# 17_-ETH_CONNECTOR.net
KiCad netlist of a schematic drawn in Altium Designer
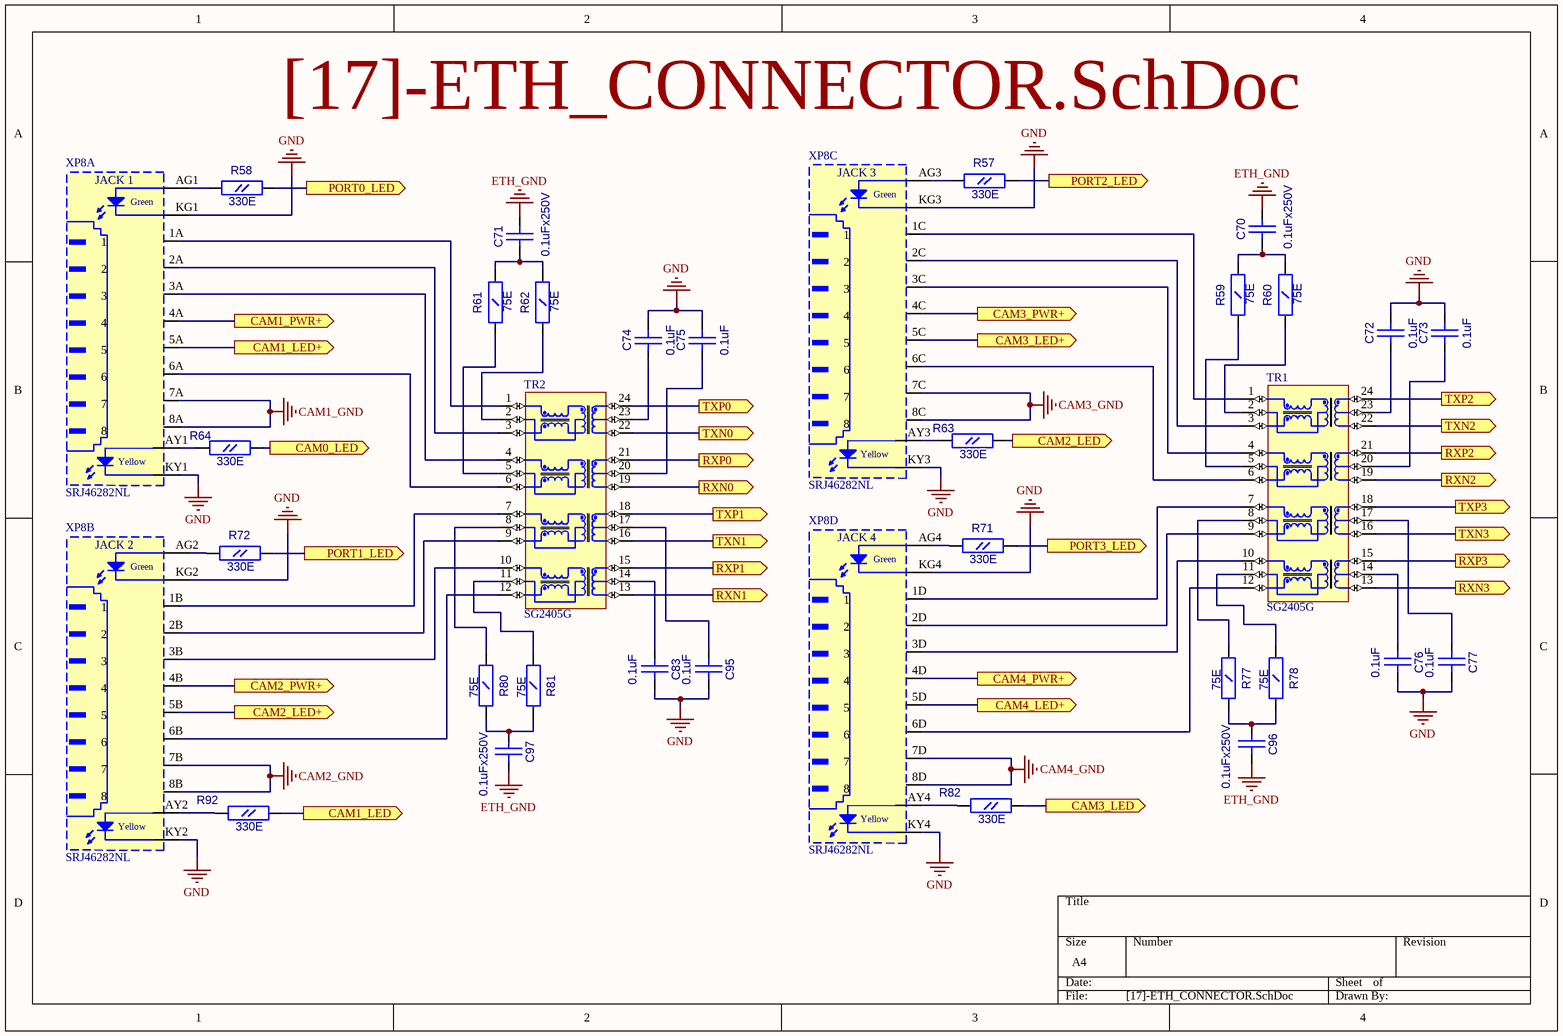
[diagram p0: [17]-ETH_CONNECTOR.SchDoc]

(export (version "E")
  (design (tool "Eeschema 10.0.6"))
  (components
    (comp (ref "C70")
      (value "0.1uFx250V")
      (footprint "CC1206")
      (description "CC1206")
      (libsource (lib "fizik_lib (1)") (part "CC1206"))
    )
    (comp (ref "C71")
      (value "0.1uFx250V")
      (footprint "CC1206")
      (description "CC1206")
      (libsource (lib "fizik_lib (1)") (part "CC1206"))
    )
    (comp (ref "C72")
      (value "0.1uF")
      (footprint "CC0603")
      (description "CC0603")
      (libsource (lib "fizik_lib") (part "CC0603"))
    )
    (comp (ref "C73")
      (value "0.1uF")
      (footprint "CC0603")
      (description "CC0603")
      (libsource (lib "fizik_lib") (part "CC0603"))
    )
    (comp (ref "C74")
      (value "0.1uF")
      (footprint "CC0603")
      (description "CC0603")
      (libsource (lib "fizik_lib") (part "CC0603"))
    )
    (comp (ref "C75")
      (value "0.1uF")
      (footprint "CC0603")
      (description "CC0603")
      (libsource (lib "fizik_lib") (part "CC0603"))
    )
    (comp (ref "C76")
      (value "0.1uF")
      (footprint "CC0603")
      (description "CC0603")
      (libsource (lib "fizik_lib") (part "CC0603"))
    )
    (comp (ref "C77")
      (value "0.1uF")
      (footprint "CC0603")
      (description "CC0603")
      (libsource (lib "fizik_lib") (part "CC0603"))
    )
    (comp (ref "C83")
      (value "0.1uF")
      (footprint "CC0603")
      (description "CC0603")
      (libsource (lib "fizik_lib") (part "CC0603"))
    )
    (comp (ref "C95")
      (value "0.1uF")
      (footprint "CC0603")
      (description "CC0603")
      (libsource (lib "fizik_lib") (part "CC0603"))
    )
    (comp (ref "C96")
      (value "0.1uFx250V")
      (footprint "CC1206")
      (description "CC1206")
      (libsource (lib "fizik_lib (1)") (part "CC1206"))
    )
    (comp (ref "C97")
      (value "0.1uFx250V")
      (footprint "CC1206")
      (description "CC1206")
      (libsource (lib "fizik_lib (1)") (part "CC1206"))
    )
    (comp (ref "R57")
      (value "330E")
      (footprint "RC0603")
      (description "RC0603")
      (libsource (lib "fizik_lib") (part "RC0603"))
    )
    (comp (ref "R58")
      (value "330E")
      (footprint "RC0603")
      (description "RC0603")
      (libsource (lib "fizik_lib") (part "RC0603"))
    )
    (comp (ref "R59")
      (value "75E")
      (footprint "RC1206")
      (description "RC1206")
      (libsource (lib "fizik_lib (1)") (part "RC1206"))
    )
    (comp (ref "R60")
      (value "75E")
      (footprint "RC1206")
      (description "RC1206")
      (libsource (lib "fizik_lib (1)") (part "RC1206"))
    )
    (comp (ref "R61")
      (value "75E")
      (footprint "RC1206")
      (description "RC1206")
      (libsource (lib "fizik_lib (1)") (part "RC1206"))
    )
    (comp (ref "R62")
      (value "75E")
      (footprint "RC1206")
      (description "RC1206")
      (libsource (lib "fizik_lib (1)") (part "RC1206"))
    )
    (comp (ref "R63")
      (value "330E")
      (footprint "RC0603")
      (description "RC0603")
      (libsource (lib "fizik_lib") (part "RC0603"))
    )
    (comp (ref "R64")
      (value "330E")
      (footprint "RC0603")
      (description "RC0603")
      (libsource (lib "fizik_lib") (part "RC0603"))
    )
    (comp (ref "R71")
      (value "330E")
      (footprint "RC0603")
      (description "RC0603")
      (libsource (lib "fizik_lib") (part "RC0603"))
    )
    (comp (ref "R72")
      (value "330E")
      (footprint "RC0603")
      (description "RC0603")
      (libsource (lib "fizik_lib") (part "RC0603"))
    )
    (comp (ref "R77")
      (value "75E")
      (footprint "RC1206")
      (description "RC1206")
      (libsource (lib "fizik_lib (1)") (part "RC1206"))
    )
    (comp (ref "R78")
      (value "75E")
      (footprint "RC1206")
      (description "RC1206")
      (libsource (lib "fizik_lib (1)") (part "RC1206"))
    )
    (comp (ref "R80")
      (value "75E")
      (footprint "RC1206")
      (description "RC1206")
      (libsource (lib "fizik_lib (1)") (part "RC1206"))
    )
    (comp (ref "R81")
      (value "75E")
      (footprint "RC1206")
      (description "RC1206")
      (libsource (lib "fizik_lib (1)") (part "RC1206"))
    )
    (comp (ref "R82")
      (value "330E")
      (footprint "RC0603")
      (description "RC0603")
      (libsource (lib "fizik_lib") (part "RC0603"))
    )
    (comp (ref "R92")
      (value "330E")
      (footprint "RC0603")
      (description "RC0603")
      (libsource (lib "fizik_lib") (part "RC0603"))
    )
    (comp (ref "TR1")
      (value "SG2405G")
      (footprint "SG2405G")
      (description "Ehternet transformer Gigabit or 2 LAN10/100")
      (libsource (lib "fizik_lib (1)") (part "SG2405G"))
    )
    (comp (ref "TR2")
      (value "SG2405G")
      (footprint "SG2405G")
      (description "Ehternet transformer Gigabit or 2 LAN10/100")
      (libsource (lib "fizik_lib (1)") (part "SG2405G"))
    )
    (comp (ref "XP8")
      (value "SRJ46282NL")
      (footprint "SRJ46282NL")
      (libsource (lib "fizik_lib (1)") (part "SRJ46282NL"))
    )
  )
  (nets
    (net (code "1") (name "/CAM0_LED") (class "Default")
      (node (ref "R64") (pin "2") (pinfunction "B_2") (pintype "passive"))
    )
    (net (code "2") (name "/CAM1_LED") (class "Default")
      (node (ref "R92") (pin "2") (pinfunction "B_2") (pintype "passive"))
    )
    (net (code "3") (name "/CAM1_LED+") (class "Default")
      (node (ref "XP8") (pin "5A") (pinfunction "1_5A") (pintype "passive"))
    )
    (net (code "4") (name "/CAM1_PWR+") (class "Default")
      (node (ref "XP8") (pin "4A") (pinfunction "1_4A") (pintype "passive"))
    )
    (net (code "5") (name "/CAM2_LED") (class "Default")
      (node (ref "R63") (pin "2") (pinfunction "B_2") (pintype "passive"))
    )
    (net (code "6") (name "/CAM2_LED+") (class "Default")
      (node (ref "XP8") (pin "5B") (pinfunction "1_5B") (pintype "passive"))
    )
    (net (code "7") (name "/CAM2_PWR+") (class "Default")
      (node (ref "XP8") (pin "4B") (pinfunction "1_4B") (pintype "passive"))
    )
    (net (code "8") (name "/CAM3_LED") (class "Default")
      (node (ref "R82") (pin "2") (pinfunction "B_2") (pintype "passive"))
    )
    (net (code "9") (name "/CAM3_LED+") (class "Default")
      (node (ref "XP8") (pin "5C") (pinfunction "1_5C") (pintype "passive"))
    )
    (net (code "10") (name "/CAM3_PWR+") (class "Default")
      (node (ref "XP8") (pin "4C") (pinfunction "1_4C") (pintype "passive"))
    )
    (net (code "11") (name "/CAM4_LED+") (class "Default")
      (node (ref "XP8") (pin "5D") (pinfunction "1_5D") (pintype "passive"))
    )
    (net (code "12") (name "/CAM4_PWR+") (class "Default")
      (node (ref "XP8") (pin "4D") (pinfunction "1_4D") (pintype "passive"))
    )
    (net (code "13") (name "/PORT0_LED") (class "Default")
      (node (ref "R58") (pin "2") (pinfunction "B_2") (pintype "passive"))
    )
    (net (code "14") (name "/PORT1_LED") (class "Default")
      (node (ref "R72") (pin "2") (pinfunction "B_2") (pintype "passive"))
    )
    (net (code "15") (name "/PORT2_LED") (class "Default")
      (node (ref "R57") (pin "2") (pinfunction "B_2") (pintype "passive"))
    )
    (net (code "16") (name "/PORT3_LED") (class "Default")
      (node (ref "R71") (pin "2") (pinfunction "B_2") (pintype "passive"))
    )
    (net (code "17") (name "/RXN0") (class "Default")
      (node (ref "TR2") (pin "19") (pinfunction "TX1-_19") (pintype "bidirectional"))
    )
    (net (code "18") (name "/RXN1") (class "Default")
      (node (ref "TR2") (pin "13") (pinfunction "RX2-_13") (pintype "bidirectional"))
    )
    (net (code "19") (name "/RXN2") (class "Default")
      (node (ref "TR1") (pin "19") (pinfunction "TX1-_19") (pintype "bidirectional"))
    )
    (net (code "20") (name "/RXN3") (class "Default")
      (node (ref "TR1") (pin "13") (pinfunction "RX2-_13") (pintype "bidirectional"))
    )
    (net (code "21") (name "/RXP0") (class "Default")
      (node (ref "TR2") (pin "21") (pinfunction "TX1+_21") (pintype "bidirectional"))
    )
    (net (code "22") (name "/RXP1") (class "Default")
      (node (ref "TR2") (pin "15") (pinfunction "RX2+_15") (pintype "bidirectional"))
    )
    (net (code "23") (name "/RXP2") (class "Default")
      (node (ref "TR1") (pin "21") (pinfunction "TX1+_21") (pintype "bidirectional"))
    )
    (net (code "24") (name "/RXP3") (class "Default")
      (node (ref "TR1") (pin "15") (pinfunction "RX2+_15") (pintype "bidirectional"))
    )
    (net (code "25") (name "/TXN0") (class "Default")
      (node (ref "TR2") (pin "22") (pinfunction "RX1-_22") (pintype "bidirectional"))
    )
    (net (code "26") (name "/TXN1") (class "Default")
      (node (ref "TR2") (pin "16") (pinfunction "TX2-_16") (pintype "bidirectional"))
    )
    (net (code "27") (name "/TXN2") (class "Default")
      (node (ref "TR1") (pin "22") (pinfunction "RX1-_22") (pintype "bidirectional"))
    )
    (net (code "28") (name "/TXN3") (class "Default")
      (node (ref "TR1") (pin "16") (pinfunction "TX2-_16") (pintype "bidirectional"))
    )
    (net (code "29") (name "/TXP0") (class "Default")
      (node (ref "TR2") (pin "24") (pinfunction "RX1+_24") (pintype "bidirectional"))
    )
    (net (code "30") (name "/TXP1") (class "Default")
      (node (ref "TR2") (pin "18") (pinfunction "TX2+_18") (pintype "bidirectional"))
    )
    (net (code "31") (name "/TXP2") (class "Default")
      (node (ref "TR1") (pin "24") (pinfunction "RX1+_24") (pintype "bidirectional"))
    )
    (net (code "32") (name "/TXP3") (class "Default")
      (node (ref "TR1") (pin "18") (pinfunction "TX2+_18") (pintype "bidirectional"))
    )
    (net (code "33") (name "CAM1_GND") (class "Default")
      (node (ref "XP8") (pin "7A") (pinfunction "1_7A") (pintype "passive"))
      (node (ref "XP8") (pin "8A") (pinfunction "1_8A") (pintype "passive"))
    )
    (net (code "34") (name "CAM2_GND") (class "Default")
      (node (ref "XP8") (pin "7B") (pinfunction "1_7B") (pintype "passive"))
      (node (ref "XP8") (pin "8B") (pinfunction "1_8B") (pintype "passive"))
    )
    (net (code "35") (name "CAM3_GND") (class "Default")
      (node (ref "XP8") (pin "7C") (pinfunction "1_7C") (pintype "passive"))
      (node (ref "XP8") (pin "8C") (pinfunction "1_8C") (pintype "passive"))
    )
    (net (code "36") (name "CAM4_GND") (class "Default")
      (node (ref "XP8") (pin "7D") (pinfunction "1_7D") (pintype "passive"))
      (node (ref "XP8") (pin "8D") (pinfunction "1_8D") (pintype "passive"))
    )
    (net (code "37") (name "ETH_GND") (class "Default")
      (node (ref "C70") (pin "2") (pinfunction "B_2") (pintype "passive"))
      (node (ref "C71") (pin "2") (pinfunction "B_2") (pintype "passive"))
      (node (ref "C96") (pin "2") (pinfunction "B_2") (pintype "passive"))
      (node (ref "C97") (pin "2") (pinfunction "B_2") (pintype "passive"))
    )
    (net (code "38") (name "GND") (class "Default")
      (node (ref "C72") (pin "2") (pinfunction "B_2") (pintype "passive"))
      (node (ref "C73") (pin "2") (pinfunction "B_2") (pintype "passive"))
      (node (ref "C74") (pin "2") (pinfunction "B_2") (pintype "passive"))
      (node (ref "C75") (pin "2") (pinfunction "B_2") (pintype "passive"))
      (node (ref "C76") (pin "2") (pinfunction "B_2") (pintype "passive"))
      (node (ref "C77") (pin "2") (pinfunction "B_2") (pintype "passive"))
      (node (ref "C83") (pin "2") (pinfunction "B_2") (pintype "passive"))
      (node (ref "C95") (pin "2") (pinfunction "B_2") (pintype "passive"))
      (node (ref "XP8") (pin "KG1") (pinfunction "D2_KG1") (pintype "passive"))
      (node (ref "XP8") (pin "KG2") (pinfunction "D2_KG2") (pintype "passive"))
      (node (ref "XP8") (pin "KG3") (pinfunction "D2_KG3") (pintype "passive"))
      (node (ref "XP8") (pin "KG4") (pinfunction "D2_KG4") (pintype "passive"))
      (node (ref "XP8") (pin "KY1") (pinfunction "D4_KY1") (pintype "passive"))
      (node (ref "XP8") (pin "KY2") (pinfunction "D4_KY2") (pintype "passive"))
      (node (ref "XP8") (pin "KY3") (pinfunction "D4_KY3") (pintype "passive"))
      (node (ref "XP8") (pin "KY4") (pinfunction "D4_KY4") (pintype "passive"))
    )
    (net (code "39") (name "Net-(C70-A)") (class "Default")
      (node (ref "C70") (pin "1") (pinfunction "A_1") (pintype "passive"))
      (node (ref "R59") (pin "2") (pinfunction "B_2") (pintype "passive"))
      (node (ref "R60") (pin "2") (pinfunction "B_2") (pintype "passive"))
    )
    (net (code "40") (name "Net-(C71-A)") (class "Default")
      (node (ref "C71") (pin "1") (pinfunction "A_1") (pintype "passive"))
      (node (ref "R61") (pin "2") (pinfunction "B_2") (pintype "passive"))
      (node (ref "R62") (pin "2") (pinfunction "B_2") (pintype "passive"))
    )
    (net (code "41") (name "Net-(C72-A)") (class "Default")
      (node (ref "C72") (pin "1") (pinfunction "A_1") (pintype "passive"))
      (node (ref "TR1") (pin "23") (pinfunction "RXCT1_23") (pintype "bidirectional"))
    )
    (net (code "42") (name "Net-(C73-A)") (class "Default")
      (node (ref "C73") (pin "1") (pinfunction "A_1") (pintype "passive"))
      (node (ref "TR1") (pin "20") (pinfunction "TXCT1_20") (pintype "bidirectional"))
    )
    (net (code "43") (name "Net-(C74-A)") (class "Default")
      (node (ref "C74") (pin "1") (pinfunction "A_1") (pintype "passive"))
      (node (ref "TR2") (pin "23") (pinfunction "RXCT1_23") (pintype "bidirectional"))
    )
    (net (code "44") (name "Net-(C75-A)") (class "Default")
      (node (ref "C75") (pin "1") (pinfunction "A_1") (pintype "passive"))
      (node (ref "TR2") (pin "20") (pinfunction "TXCT1_20") (pintype "bidirectional"))
    )
    (net (code "45") (name "Net-(C76-A)") (class "Default")
      (node (ref "C76") (pin "1") (pinfunction "A_1") (pintype "passive"))
      (node (ref "TR1") (pin "14") (pinfunction "RXCT2_14") (pintype "bidirectional"))
    )
    (net (code "46") (name "Net-(C77-A)") (class "Default")
      (node (ref "C77") (pin "1") (pinfunction "A_1") (pintype "passive"))
      (node (ref "TR1") (pin "17") (pinfunction "TXCT2_17") (pintype "bidirectional"))
    )
    (net (code "47") (name "Net-(C83-A)") (class "Default")
      (node (ref "C83") (pin "1") (pinfunction "A_1") (pintype "passive"))
      (node (ref "TR2") (pin "14") (pinfunction "RXCT2_14") (pintype "bidirectional"))
    )
    (net (code "48") (name "Net-(C95-A)") (class "Default")
      (node (ref "C95") (pin "1") (pinfunction "A_1") (pintype "passive"))
      (node (ref "TR2") (pin "17") (pinfunction "TXCT2_17") (pintype "bidirectional"))
    )
    (net (code "49") (name "Net-(C96-A)") (class "Default")
      (node (ref "C96") (pin "1") (pinfunction "A_1") (pintype "passive"))
      (node (ref "R77") (pin "2") (pinfunction "B_2") (pintype "passive"))
      (node (ref "R78") (pin "2") (pinfunction "B_2") (pintype "passive"))
    )
    (net (code "50") (name "Net-(C97-A)") (class "Default")
      (node (ref "C97") (pin "1") (pinfunction "A_1") (pintype "passive"))
      (node (ref "R80") (pin "2") (pinfunction "B_2") (pintype "passive"))
      (node (ref "R81") (pin "2") (pinfunction "B_2") (pintype "passive"))
    )
    (net (code "51") (name "Net-(R57-A)") (class "Default")
      (node (ref "R57") (pin "1") (pinfunction "A_1") (pintype "passive"))
      (node (ref "XP8") (pin "AG3") (pinfunction "D1_AG3") (pintype "passive"))
    )
    (net (code "52") (name "Net-(R58-A)") (class "Default")
      (node (ref "R58") (pin "1") (pinfunction "A_1") (pintype "passive"))
      (node (ref "XP8") (pin "AG1") (pinfunction "D1_AG1") (pintype "passive"))
    )
    (net (code "53") (name "Net-(R59-A)") (class "Default")
      (node (ref "R59") (pin "1") (pinfunction "A_1") (pintype "passive"))
      (node (ref "TR1") (pin "5") (pinfunction "TCT1_5") (pintype "bidirectional"))
    )
    (net (code "54") (name "Net-(R60-A)") (class "Default")
      (node (ref "R60") (pin "1") (pinfunction "A_1") (pintype "passive"))
      (node (ref "TR1") (pin "2") (pinfunction "RCT1_2") (pintype "bidirectional"))
    )
    (net (code "55") (name "Net-(R61-A)") (class "Default")
      (node (ref "R61") (pin "1") (pinfunction "A_1") (pintype "passive"))
      (node (ref "TR2") (pin "5") (pinfunction "TCT1_5") (pintype "bidirectional"))
    )
    (net (code "56") (name "Net-(R62-A)") (class "Default")
      (node (ref "R62") (pin "1") (pinfunction "A_1") (pintype "passive"))
      (node (ref "TR2") (pin "2") (pinfunction "RCT1_2") (pintype "bidirectional"))
    )
    (net (code "57") (name "Net-(R63-A)") (class "Default")
      (node (ref "R63") (pin "1") (pinfunction "A_1") (pintype "passive"))
      (node (ref "XP8") (pin "AY3") (pinfunction "D3_AY3") (pintype "passive"))
    )
    (net (code "58") (name "Net-(R64-A)") (class "Default")
      (node (ref "R64") (pin "1") (pinfunction "A_1") (pintype "passive"))
      (node (ref "XP8") (pin "AY1") (pinfunction "D3_AY1") (pintype "passive"))
    )
    (net (code "59") (name "Net-(R71-A)") (class "Default")
      (node (ref "R71") (pin "1") (pinfunction "A_1") (pintype "passive"))
      (node (ref "XP8") (pin "AG4") (pinfunction "D1_AG4") (pintype "passive"))
    )
    (net (code "60") (name "Net-(R72-A)") (class "Default")
      (node (ref "R72") (pin "1") (pinfunction "A_1") (pintype "passive"))
      (node (ref "XP8") (pin "AG2") (pinfunction "D1_AG2") (pintype "passive"))
    )
    (net (code "61") (name "Net-(R77-A)") (class "Default")
      (node (ref "R77") (pin "1") (pinfunction "A_1") (pintype "passive"))
      (node (ref "TR1") (pin "8") (pinfunction "TCT2_8") (pintype "bidirectional"))
    )
    (net (code "62") (name "Net-(R78-A)") (class "Default")
      (node (ref "R78") (pin "1") (pinfunction "A_1") (pintype "passive"))
      (node (ref "TR1") (pin "11") (pinfunction "RCT2_11") (pintype "bidirectional"))
    )
    (net (code "63") (name "Net-(R80-A)") (class "Default")
      (node (ref "R80") (pin "1") (pinfunction "A_1") (pintype "passive"))
      (node (ref "TR2") (pin "8") (pinfunction "TCT2_8") (pintype "bidirectional"))
    )
    (net (code "64") (name "Net-(R81-A)") (class "Default")
      (node (ref "R81") (pin "1") (pinfunction "A_1") (pintype "passive"))
      (node (ref "TR2") (pin "11") (pinfunction "RCT2_11") (pintype "bidirectional"))
    )
    (net (code "65") (name "Net-(R82-A)") (class "Default")
      (node (ref "R82") (pin "1") (pinfunction "A_1") (pintype "passive"))
      (node (ref "XP8") (pin "AY4") (pinfunction "D3_AY4") (pintype "passive"))
    )
    (net (code "66") (name "Net-(R92-A)") (class "Default")
      (node (ref "R92") (pin "1") (pinfunction "A_1") (pintype "passive"))
      (node (ref "XP8") (pin "AY2") (pinfunction "D3_AY2") (pintype "passive"))
    )
    (net (code "67") (name "Net-(TR1-RD1+)") (class "Default")
      (node (ref "TR1") (pin "1") (pinfunction "RD1+_1") (pintype "bidirectional"))
      (node (ref "XP8") (pin "1C") (pinfunction "1_1C") (pintype "passive"))
    )
    (net (code "68") (name "Net-(TR1-RD1-)") (class "Default")
      (node (ref "TR1") (pin "3") (pinfunction "RD1-_3") (pintype "bidirectional"))
      (node (ref "XP8") (pin "2C") (pinfunction "1_2C") (pintype "passive"))
    )
    (net (code "69") (name "Net-(TR1-RD2+)") (class "Default")
      (node (ref "TR1") (pin "10") (pinfunction "RD2+_10") (pintype "bidirectional"))
      (node (ref "XP8") (pin "3D") (pinfunction "1_3D") (pintype "passive"))
    )
    (net (code "70") (name "Net-(TR1-RD2-)") (class "Default")
      (node (ref "TR1") (pin "12") (pinfunction "RD2-_12") (pintype "bidirectional"))
      (node (ref "XP8") (pin "6D") (pinfunction "1_6D") (pintype "passive"))
    )
    (net (code "71") (name "Net-(TR1-TD1+)") (class "Default")
      (node (ref "TR1") (pin "4") (pinfunction "TD1+_4") (pintype "bidirectional"))
      (node (ref "XP8") (pin "3C") (pinfunction "1_3C") (pintype "passive"))
    )
    (net (code "72") (name "Net-(TR1-TD1-)") (class "Default")
      (node (ref "TR1") (pin "6") (pinfunction "TD1-_6") (pintype "bidirectional"))
      (node (ref "XP8") (pin "6C") (pinfunction "1_6C") (pintype "passive"))
    )
    (net (code "73") (name "Net-(TR1-TD2+)") (class "Default")
      (node (ref "TR1") (pin "7") (pinfunction "TD2+_7") (pintype "bidirectional"))
      (node (ref "XP8") (pin "1D") (pinfunction "1_1D") (pintype "passive"))
    )
    (net (code "74") (name "Net-(TR1-TD2-)") (class "Default")
      (node (ref "TR1") (pin "9") (pinfunction "TD2-_9") (pintype "bidirectional"))
      (node (ref "XP8") (pin "2D") (pinfunction "1_2D") (pintype "passive"))
    )
    (net (code "75") (name "Net-(TR2-RD1+)") (class "Default")
      (node (ref "TR2") (pin "1") (pinfunction "RD1+_1") (pintype "bidirectional"))
      (node (ref "XP8") (pin "1A") (pinfunction "1_1A") (pintype "passive"))
    )
    (net (code "76") (name "Net-(TR2-RD1-)") (class "Default")
      (node (ref "TR2") (pin "3") (pinfunction "RD1-_3") (pintype "bidirectional"))
      (node (ref "XP8") (pin "2A") (pinfunction "1_2A") (pintype "passive"))
    )
    (net (code "77") (name "Net-(TR2-RD2+)") (class "Default")
      (node (ref "TR2") (pin "10") (pinfunction "RD2+_10") (pintype "bidirectional"))
      (node (ref "XP8") (pin "3B") (pinfunction "1_3B") (pintype "passive"))
    )
    (net (code "78") (name "Net-(TR2-RD2-)") (class "Default")
      (node (ref "TR2") (pin "12") (pinfunction "RD2-_12") (pintype "bidirectional"))
      (node (ref "XP8") (pin "6B") (pinfunction "1_6B") (pintype "passive"))
    )
    (net (code "79") (name "Net-(TR2-TD1+)") (class "Default")
      (node (ref "TR2") (pin "4") (pinfunction "TD1+_4") (pintype "bidirectional"))
      (node (ref "XP8") (pin "3A") (pinfunction "1_3A") (pintype "passive"))
    )
    (net (code "80") (name "Net-(TR2-TD1-)") (class "Default")
      (node (ref "TR2") (pin "6") (pinfunction "TD1-_6") (pintype "bidirectional"))
      (node (ref "XP8") (pin "6A") (pinfunction "1_6A") (pintype "passive"))
    )
    (net (code "81") (name "Net-(TR2-TD2+)") (class "Default")
      (node (ref "TR2") (pin "7") (pinfunction "TD2+_7") (pintype "bidirectional"))
      (node (ref "XP8") (pin "1B") (pinfunction "1_1B") (pintype "passive"))
    )
    (net (code "82") (name "Net-(TR2-TD2-)") (class "Default")
      (node (ref "TR2") (pin "9") (pinfunction "TD2-_9") (pintype "bidirectional"))
      (node (ref "XP8") (pin "2B") (pinfunction "1_2B") (pintype "passive"))
    )
  )
)
